# teensyMotors.net
KiCad netlist of a schematic drawn in EAGLE
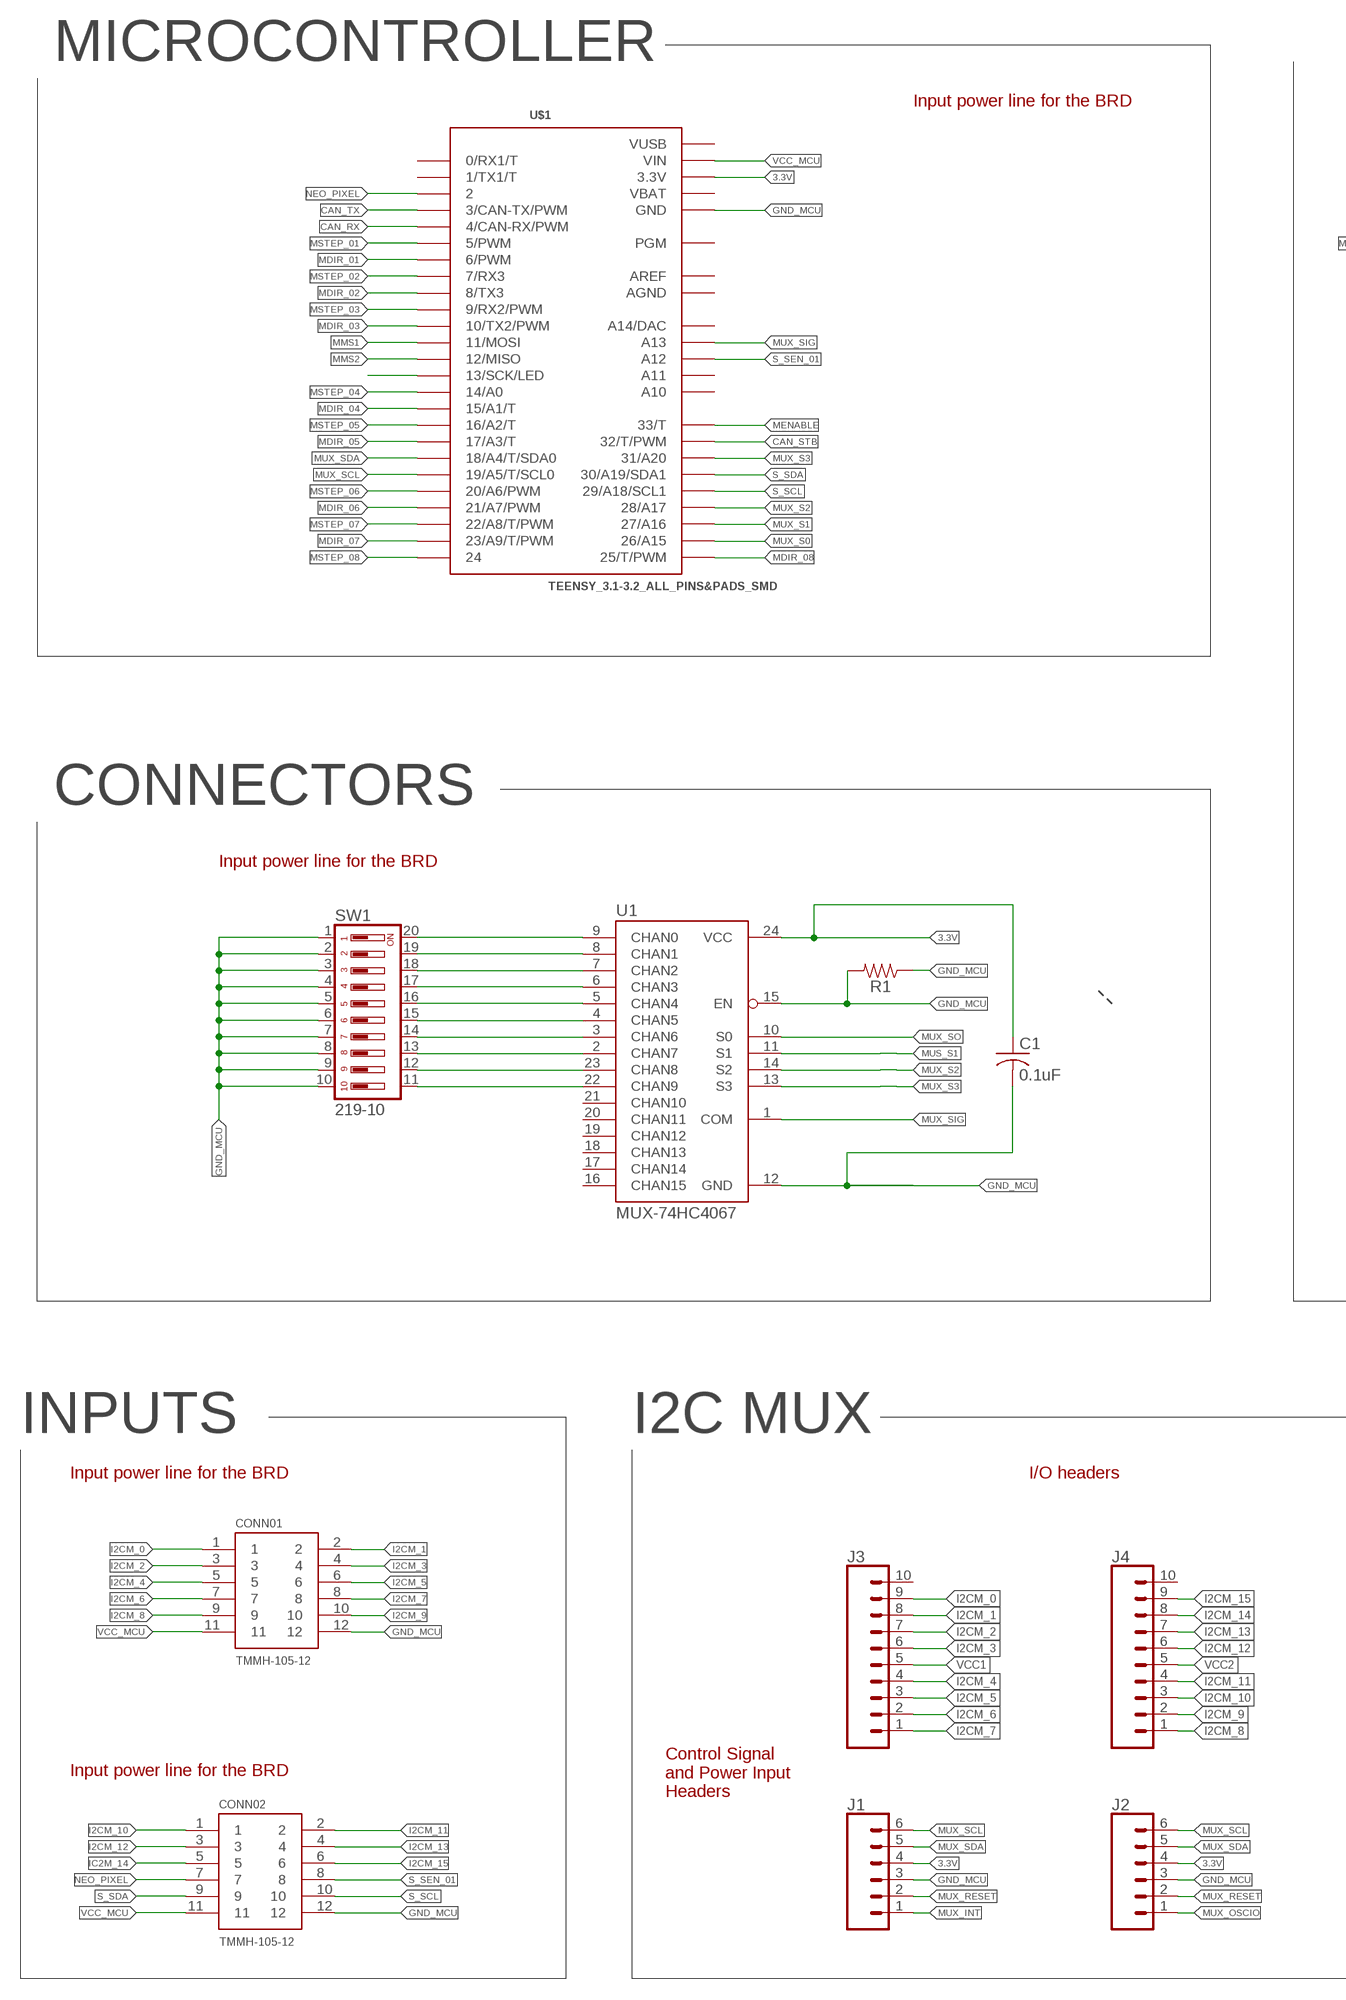
[diagram p0: schematic, sheet 1, part 1 of 2]
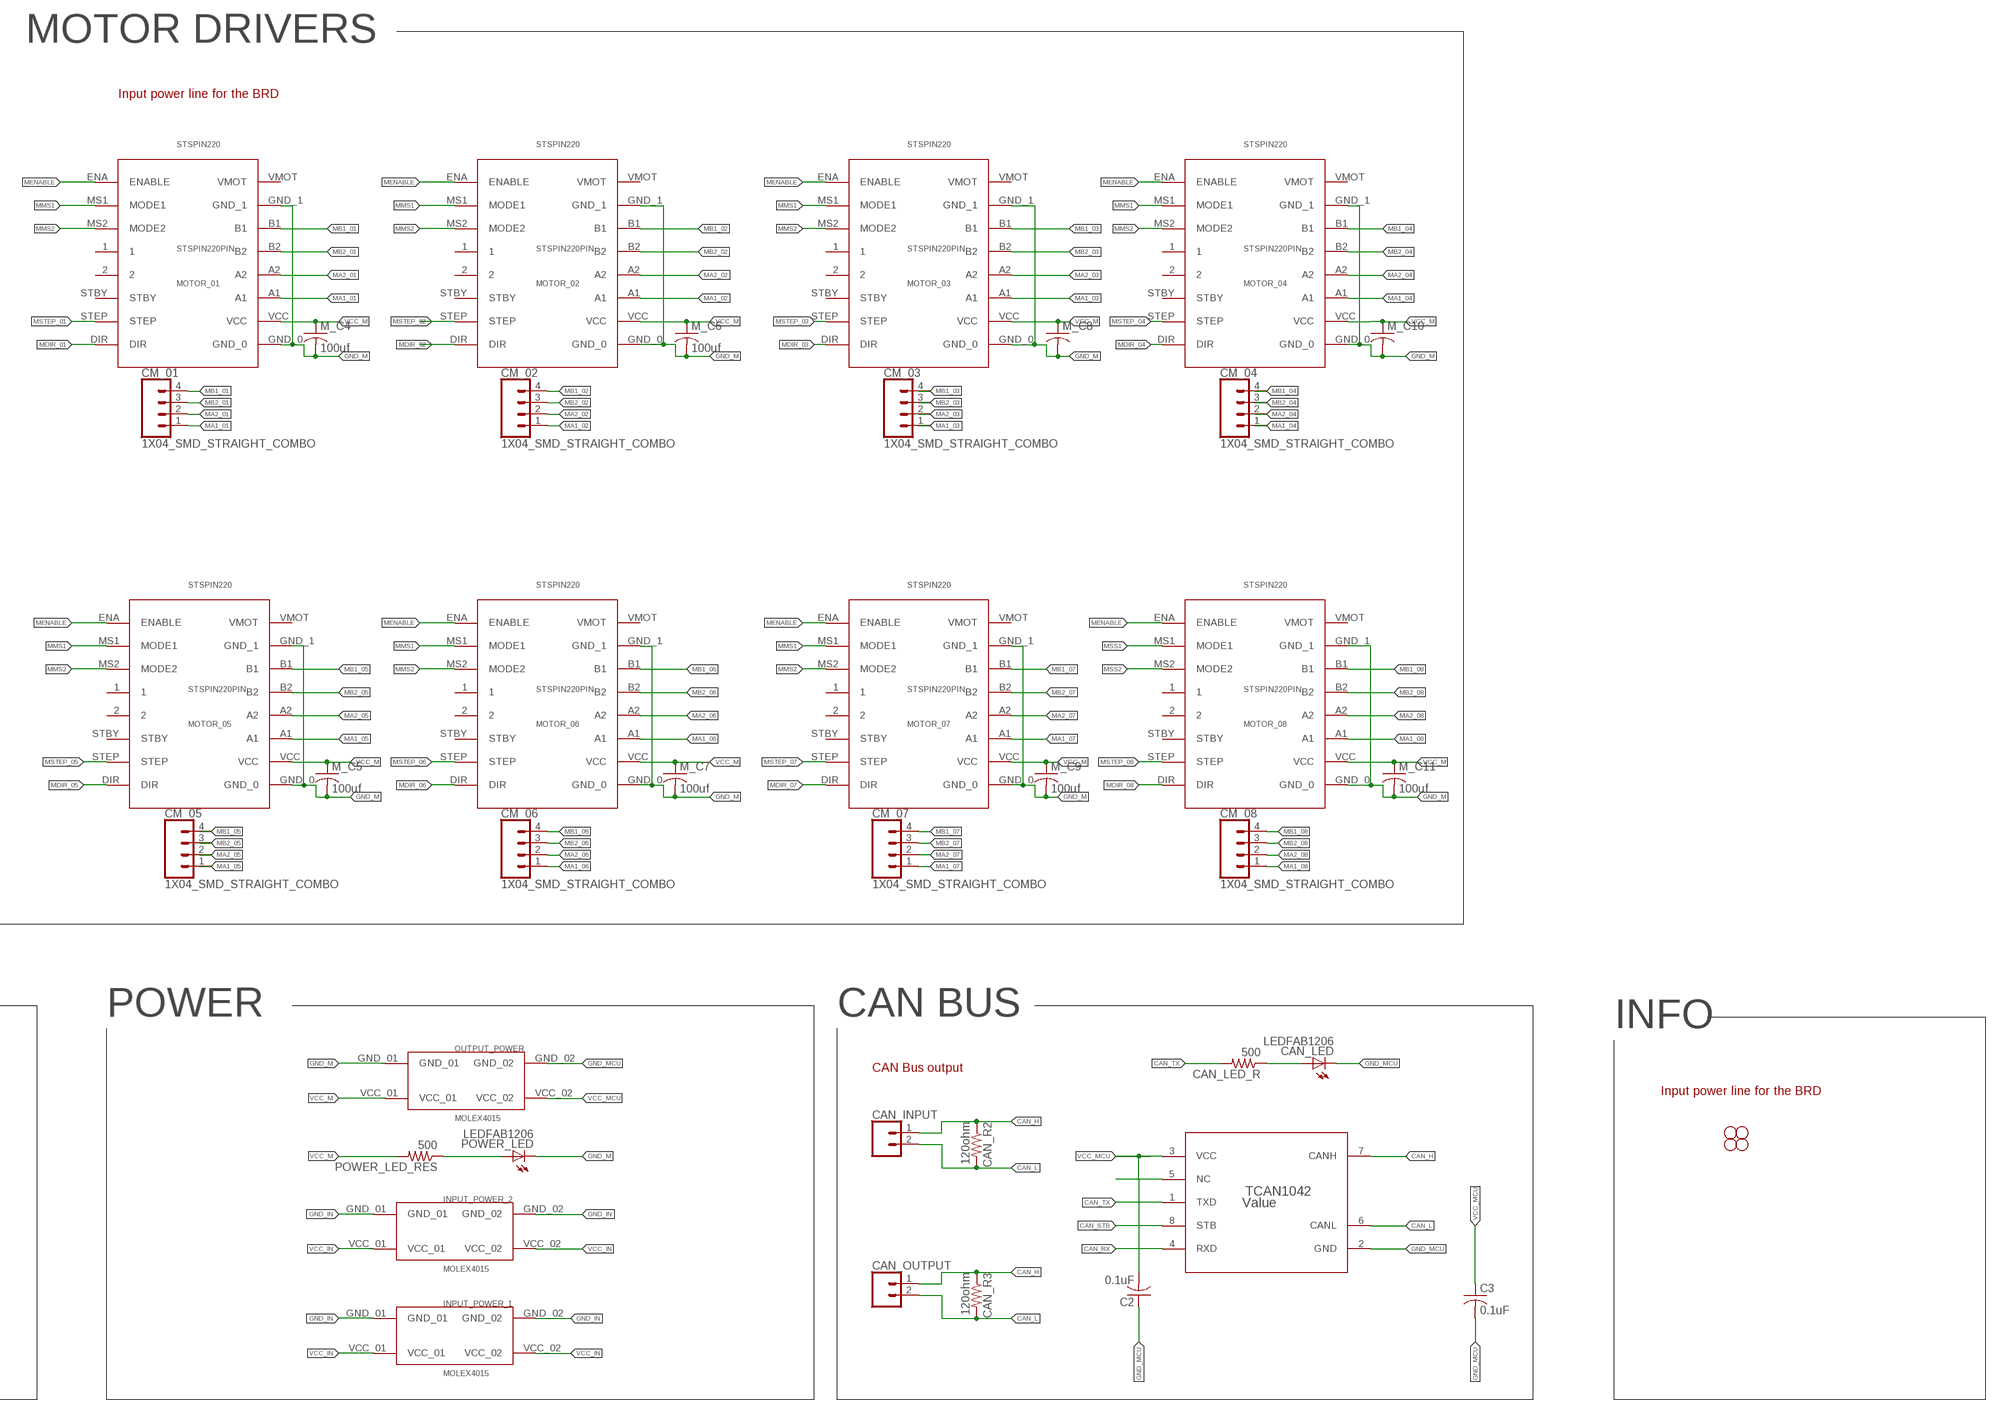
[diagram p1: schematic, sheet 1, part 2 of 2]

(export (version "E")
  (design (tool "Eeschema 10.0.6"))
  (components
    (comp (ref "C1")
      (value "0.1uF")
      (footprint "eagle-import:C1206")
      (libsource (lib "eagle-import") (part "C-USC1206"))
    )
    (comp (ref "C2")
      (value "0.1uF")
      (footprint "eagle-import:C1206")
      (libsource (lib "eagle-import") (part "C-USC1206"))
    )
    (comp (ref "C3")
      (value "0.1uF")
      (footprint "eagle-import:C1206")
      (libsource (lib "eagle-import") (part "C-USC1206"))
    )
    (comp (ref "CAN_INPUT")
      (value "CONN_02-JST-2MM-SMT")
      (footprint "eagle-import:JST-2-SMD")
      (libsource (lib "eagle-import") (part "CONN_02-JST-2MM-SMT"))
    )
    (comp (ref "CAN_LED")
      (value "LEDFAB1206")
      (footprint "eagle-import:LED1206FAB")
      (libsource (lib "eagle-import") (part "LEDFAB1206"))
    )
    (comp (ref "CAN_LED_R")
      (value "500")
      (footprint "eagle-import:R1206FAB")
      (libsource (lib "eagle-import") (part "RES-US1206FAB"))
    )
    (comp (ref "CAN_OUTPUT")
      (value "CONN_02-JST-2MM-SMT")
      (footprint "eagle-import:JST-2-SMD")
      (libsource (lib "eagle-import") (part "CONN_02-JST-2MM-SMT"))
    )
    (comp (ref "CAN_R2")
      (value "120ohm")
      (footprint "eagle-import:1206")
      (libsource (lib "eagle-import") (part "RESISTOR1206"))
    )
    (comp (ref "CAN_R3")
      (value "120ohm")
      (footprint "eagle-import:1206")
      (libsource (lib "eagle-import") (part "RESISTOR1206"))
    )
    (comp (ref "CM_01")
      (value "1X04_SMD_STRAIGHT_COMBO")
      (footprint "eagle-import:1X04_SMD_VERTICAL_COMBO")
      (libsource (lib "eagle-import") (part "CONN_04SMD_STRAIGHT_COMBO"))
    )
    (comp (ref "CM_02")
      (value "1X04_SMD_STRAIGHT_COMBO")
      (footprint "eagle-import:1X04_SMD_VERTICAL_COMBO")
      (libsource (lib "eagle-import") (part "CONN_04SMD_STRAIGHT_COMBO"))
    )
    (comp (ref "CM_03")
      (value "1X04_SMD_STRAIGHT_COMBO")
      (footprint "eagle-import:1X04_SMD_VERTICAL_COMBO")
      (libsource (lib "eagle-import") (part "CONN_04SMD_STRAIGHT_COMBO"))
    )
    (comp (ref "CM_04")
      (value "1X04_SMD_STRAIGHT_COMBO")
      (footprint "eagle-import:1X04_SMD_VERTICAL_COMBO")
      (libsource (lib "eagle-import") (part "CONN_04SMD_STRAIGHT_COMBO"))
    )
    (comp (ref "CM_05")
      (value "1X04_SMD_STRAIGHT_COMBO")
      (footprint "eagle-import:1X04_SMD_VERTICAL_COMBO")
      (libsource (lib "eagle-import") (part "CONN_04SMD_STRAIGHT_COMBO"))
    )
    (comp (ref "CM_06")
      (value "1X04_SMD_STRAIGHT_COMBO")
      (footprint "eagle-import:1X04_SMD_VERTICAL_COMBO")
      (libsource (lib "eagle-import") (part "CONN_04SMD_STRAIGHT_COMBO"))
    )
    (comp (ref "CM_07")
      (value "1X04_SMD_STRAIGHT_COMBO")
      (footprint "eagle-import:1X04_SMD_VERTICAL_COMBO")
      (libsource (lib "eagle-import") (part "CONN_04SMD_STRAIGHT_COMBO"))
    )
    (comp (ref "CM_08")
      (value "1X04_SMD_STRAIGHT_COMBO")
      (footprint "eagle-import:1X04_SMD_VERTICAL_COMBO")
      (libsource (lib "eagle-import") (part "CONN_04SMD_STRAIGHT_COMBO"))
    )
    (comp (ref "CONN01")
      (value "TMMH-105-12")
      (footprint "eagle-import:TMMH-105-12")
      (libsource (lib "eagle-import") (part "TMMH-105-12"))
    )
    (comp (ref "CONN02")
      (value "TMMH-105-12")
      (footprint "eagle-import:TMMH-105-12")
      (libsource (lib "eagle-import") (part "TMMH-105-12"))
    )
    (comp (ref "INPUT_POWER_1")
      (value "MOLEX4015")
      (footprint "eagle-import:MOLEX4015")
      (libsource (lib "eagle-import") (part "MOLEX4015"))
    )
    (comp (ref "INPUT_POWER_2")
      (value "MOLEX4015")
      (footprint "eagle-import:MOLEX4015")
      (libsource (lib "eagle-import") (part "MOLEX4015"))
    )
    (comp (ref "J1")
      (value "CONN_06SMD_MALE")
      (footprint "eagle-import:1X06_SMD_MALE")
      (libsource (lib "eagle-import") (part "CONN_06SMD_MALE"))
    )
    (comp (ref "J2")
      (value "CONN_06SMD_MALE")
      (footprint "eagle-import:1X06_SMD_MALE")
      (libsource (lib "eagle-import") (part "CONN_06SMD_MALE"))
    )
    (comp (ref "J3")
      (value "CONN_10SMD_MALE")
      (footprint "eagle-import:1X10_SMD_MALE")
      (libsource (lib "eagle-import") (part "CONN_10SMD_MALE"))
    )
    (comp (ref "J4")
      (value "CONN_10SMD_MALE")
      (footprint "eagle-import:1X10_SMD_MALE")
      (libsource (lib "eagle-import") (part "CONN_10SMD_MALE"))
    )
    (comp (ref "MOTOR_01")
      (value "STSPIN220PIN")
      (footprint "eagle-import:STSPIN220")
      (libsource (lib "eagle-import") (part "STSPIN220PIN"))
    )
    (comp (ref "MOTOR_02")
      (value "STSPIN220PIN")
      (footprint "eagle-import:STSPIN220")
      (libsource (lib "eagle-import") (part "STSPIN220PIN"))
    )
    (comp (ref "MOTOR_03")
      (value "STSPIN220PIN")
      (footprint "eagle-import:STSPIN220")
      (libsource (lib "eagle-import") (part "STSPIN220PIN"))
    )
    (comp (ref "MOTOR_04")
      (value "STSPIN220PIN")
      (footprint "eagle-import:STSPIN220")
      (libsource (lib "eagle-import") (part "STSPIN220PIN"))
    )
    (comp (ref "MOTOR_05")
      (value "STSPIN220PIN")
      (footprint "eagle-import:STSPIN220")
      (libsource (lib "eagle-import") (part "STSPIN220PIN"))
    )
    (comp (ref "MOTOR_06")
      (value "STSPIN220PIN")
      (footprint "eagle-import:STSPIN220")
      (libsource (lib "eagle-import") (part "STSPIN220PIN"))
    )
    (comp (ref "MOTOR_07")
      (value "STSPIN220PIN")
      (footprint "eagle-import:STSPIN220")
      (libsource (lib "eagle-import") (part "STSPIN220PIN"))
    )
    (comp (ref "MOTOR_08")
      (value "STSPIN220PIN")
      (footprint "eagle-import:STSPIN220")
      (libsource (lib "eagle-import") (part "STSPIN220PIN"))
    )
    (comp (ref "M_C4")
      (value "100uf")
      (footprint "eagle-import:C1206")
      (libsource (lib "eagle-import") (part "C-USC1206"))
    )
    (comp (ref "M_C5")
      (value "100uf")
      (footprint "eagle-import:C1206")
      (libsource (lib "eagle-import") (part "C-USC1206"))
    )
    (comp (ref "M_C6")
      (value "100uf")
      (footprint "eagle-import:C1206")
      (libsource (lib "eagle-import") (part "C-USC1206"))
    )
    (comp (ref "M_C7")
      (value "100uf")
      (footprint "eagle-import:C1206")
      (libsource (lib "eagle-import") (part "C-USC1206"))
    )
    (comp (ref "M_C8")
      (value "C-USC1206")
      (footprint "eagle-import:C1206")
      (libsource (lib "eagle-import") (part "C-USC1206"))
    )
    (comp (ref "M_C9")
      (value "100uf")
      (footprint "eagle-import:C1206")
      (libsource (lib "eagle-import") (part "C-USC1206"))
    )
    (comp (ref "M_C10")
      (value "C-USC1206")
      (footprint "eagle-import:C1206")
      (libsource (lib "eagle-import") (part "C-USC1206"))
    )
    (comp (ref "M_C11")
      (value "100uf")
      (footprint "eagle-import:C1206")
      (libsource (lib "eagle-import") (part "C-USC1206"))
    )
    (comp (ref "OUTPUT_POWER")
      (value "MOLEX4015")
      (footprint "eagle-import:MOLEX4015")
      (libsource (lib "eagle-import") (part "MOLEX4015"))
    )
    (comp (ref "POWER_LED")
      (value "LEDFAB1206")
      (footprint "eagle-import:LED1206FAB")
      (libsource (lib "eagle-import") (part "LEDFAB1206"))
    )
    (comp (ref "POWER_LED_RES")
      (value "500")
      (footprint "eagle-import:R1206FAB")
      (libsource (lib "eagle-import") (part "RES-US1206FAB"))
    )
    (comp (ref "R1")
      (value "RESISTOR1206")
      (footprint "eagle-import:1206")
      (libsource (lib "eagle-import") (part "RESISTOR1206"))
    )
    (comp (ref "STANDOFF5")
      (value "STAND-OFF")
      (footprint "eagle-import:STAND-OFF")
      (libsource (lib "eagle-import") (part "STAND-OFF"))
    )
    (comp (ref "STANDOFF6")
      (value "STAND-OFF")
      (footprint "eagle-import:STAND-OFF")
      (libsource (lib "eagle-import") (part "STAND-OFF"))
    )
    (comp (ref "STANDOFF7")
      (value "STAND-OFF")
      (footprint "eagle-import:STAND-OFF")
      (libsource (lib "eagle-import") (part "STAND-OFF"))
    )
    (comp (ref "STANDOFF8")
      (value "STAND-OFF")
      (footprint "eagle-import:STAND-OFF")
      (libsource (lib "eagle-import") (part "STAND-OFF"))
    )
    (comp (ref "SW1")
      (value "219-10")
      (footprint "eagle-import:CTS-219-10")
      (fields (field (name "MF") "SLI (CML/IDI)") (field (name "MPN") "219-10PK"))
      (libsource (lib "eagle-import") (part "219-10"))
    )
    (comp (ref "TCAN1042")
      (value "Value")
      (footprint "eagle-import:D0008A_N")
      (fields (field (name "MANUFACTURER") "Texas Instruments") (field (name "PARTNUMBER") "TCAN1042DRQ1"))
      (libsource (lib "eagle-import") (part "TCAN1042DRQ1"))
    )
    (comp (ref "U$1")
      (value "TEENSY_3.1-3.2_ALL_PINS&PADS_SMD")
      (footprint "eagle-import:TEENSY_3.0-3.2_ALL_PINS_&_PADS_SMD")
      (libsource (lib "eagle-import") (part "TEENSY_3.1-3.2_ALL_PINS&PADS_SMD"))
    )
    (comp (ref "U1")
      (value "MUX-74HC4067")
      (footprint "eagle-import:SSOP24")
      (libsource (lib "eagle-import") (part "MUX-74HC4067SMD"))
    )
  )
  (nets
    (net (code "1") (name "/AGND") (class "Default")
      (node (ref "U$1") (pin "AGND") (pinfunction "AGND_AGND") (pintype "power_in"))
    )
    (net (code "2") (name "/AREF") (class "Default")
      (node (ref "U$1") (pin "AREF") (pinfunction "AREF_AREF") (pintype "power_in"))
    )
    (net (code "3") (name "/VBAT") (class "Default")
      (node (ref "U$1") (pin "VBAT") (pinfunction "VBAT_VBAT") (pintype "power_in"))
    )
    (net (code "4") (name "/VUSB") (class "Default")
      (node (ref "U$1") (pin "VUSB") (pinfunction "VUSB_VUSB") (pintype "power_in"))
    )
    (net (code "5") (name "3.3V") (class "Default")
      (node (ref "C1") (pin "1") (pinfunction "1_1") (pintype "passive"))
      (node (ref "J1") (pin "4") (pinfunction "4_4") (pintype "passive"))
      (node (ref "J2") (pin "4") (pinfunction "4_4") (pintype "passive"))
      (node (ref "U$1") (pin "3.3V") (pinfunction "3.3V_3.3V") (pintype "power_in"))
      (node (ref "U$1") (pin "3.3V1") (pinfunction "3.3V_3.3V1") (pintype "power_in"))
      (node (ref "U$1") (pin "3.3V2") (pinfunction "3.3V_3.3V2") (pintype "power_in"))
      (node (ref "U1") (pin "24") (pinfunction "VCC_24") (pintype "bidirectional"))
    )
    (net (code "6") (name "CAN_H") (class "Default")
      (node (ref "CAN_INPUT") (pin "1") (pinfunction "2_1") (pintype "passive"))
      (node (ref "CAN_OUTPUT") (pin "1") (pinfunction "2_1") (pintype "passive"))
      (node (ref "CAN_R2") (pin "1") (pinfunction "1_1") (pintype "passive"))
      (node (ref "CAN_R3") (pin "1") (pinfunction "1_1") (pintype "passive"))
      (node (ref "TCAN1042") (pin "7") (pinfunction "CANH_7") (pintype "bidirectional"))
    )
    (net (code "7") (name "CAN_L") (class "Default")
      (node (ref "CAN_INPUT") (pin "2") (pinfunction "1_2") (pintype "passive"))
      (node (ref "CAN_OUTPUT") (pin "2") (pinfunction "1_2") (pintype "passive"))
      (node (ref "CAN_R2") (pin "2") (pinfunction "2_2") (pintype "passive"))
      (node (ref "CAN_R3") (pin "2") (pinfunction "2_2") (pintype "passive"))
      (node (ref "TCAN1042") (pin "6") (pinfunction "CANL_6") (pintype "bidirectional"))
    )
    (net (code "8") (name "CAN_RX") (class "Default")
      (node (ref "TCAN1042") (pin "4") (pinfunction "RXD_4") (pintype "output"))
      (node (ref "U$1") (pin "4") (pinfunction "4/CAN-RX/PWM_4") (pintype "bidirectional"))
    )
    (net (code "9") (name "CAN_STB") (class "Default")
      (node (ref "TCAN1042") (pin "8") (pinfunction "STB_8") (pintype "input"))
      (node (ref "U$1") (pin "32") (pinfunction "32/T/PWM_32") (pintype "bidirectional"))
    )
    (net (code "10") (name "CAN_TX") (class "Default")
      (node (ref "CAN_LED_R") (pin "2") (pinfunction "2_2") (pintype "passive"))
      (node (ref "TCAN1042") (pin "1") (pinfunction "TXD_1") (pintype "input"))
      (node (ref "U$1") (pin "3") (pinfunction "3/CAN-TX/PWM_3") (pintype "bidirectional"))
    )
    (net (code "11") (name "GND_IN") (class "Default")
      (node (ref "INPUT_POWER_1") (pin "GND_01") (pinfunction "GND_01_GND_01") (pintype "bidirectional"))
      (node (ref "INPUT_POWER_1") (pin "GND_02") (pinfunction "GND_02_GND_02") (pintype "bidirectional"))
      (node (ref "INPUT_POWER_2") (pin "GND_01") (pinfunction "GND_01_GND_01") (pintype "bidirectional"))
      (node (ref "INPUT_POWER_2") (pin "GND_02") (pinfunction "GND_02_GND_02") (pintype "bidirectional"))
    )
    (net (code "12") (name "GND_M") (class "Default")
      (node (ref "MOTOR_01") (pin "GND_0") (pinfunction "GND_0_GND_0") (pintype "bidirectional"))
      (node (ref "MOTOR_01") (pin "GND_1") (pinfunction "GND_1_GND_1") (pintype "bidirectional"))
      (node (ref "MOTOR_02") (pin "GND_0") (pinfunction "GND_0_GND_0") (pintype "bidirectional"))
      (node (ref "MOTOR_02") (pin "GND_1") (pinfunction "GND_1_GND_1") (pintype "bidirectional"))
      (node (ref "MOTOR_03") (pin "GND_0") (pinfunction "GND_0_GND_0") (pintype "bidirectional"))
      (node (ref "MOTOR_03") (pin "GND_1") (pinfunction "GND_1_GND_1") (pintype "bidirectional"))
      (node (ref "MOTOR_04") (pin "GND_0") (pinfunction "GND_0_GND_0") (pintype "bidirectional"))
      (node (ref "MOTOR_04") (pin "GND_1") (pinfunction "GND_1_GND_1") (pintype "bidirectional"))
      (node (ref "MOTOR_05") (pin "GND_0") (pinfunction "GND_0_GND_0") (pintype "bidirectional"))
      (node (ref "MOTOR_05") (pin "GND_1") (pinfunction "GND_1_GND_1") (pintype "bidirectional"))
      (node (ref "MOTOR_06") (pin "GND_0") (pinfunction "GND_0_GND_0") (pintype "bidirectional"))
      (node (ref "MOTOR_06") (pin "GND_1") (pinfunction "GND_1_GND_1") (pintype "bidirectional"))
      (node (ref "MOTOR_07") (pin "GND_0") (pinfunction "GND_0_GND_0") (pintype "bidirectional"))
      (node (ref "MOTOR_07") (pin "GND_1") (pinfunction "GND_1_GND_1") (pintype "bidirectional"))
      (node (ref "MOTOR_08") (pin "GND_0") (pinfunction "GND_0_GND_0") (pintype "bidirectional"))
      (node (ref "MOTOR_08") (pin "GND_1") (pinfunction "GND_1_GND_1") (pintype "bidirectional"))
      (node (ref "M_C10") (pin "2") (pinfunction "2_2") (pintype "passive"))
      (node (ref "M_C11") (pin "2") (pinfunction "2_2") (pintype "passive"))
      (node (ref "M_C4") (pin "2") (pinfunction "2_2") (pintype "passive"))
      (node (ref "M_C5") (pin "2") (pinfunction "2_2") (pintype "passive"))
      (node (ref "M_C6") (pin "2") (pinfunction "2_2") (pintype "passive"))
      (node (ref "M_C7") (pin "2") (pinfunction "2_2") (pintype "passive"))
      (node (ref "M_C8") (pin "2") (pinfunction "2_2") (pintype "passive"))
      (node (ref "M_C9") (pin "2") (pinfunction "2_2") (pintype "passive"))
      (node (ref "OUTPUT_POWER") (pin "GND_01") (pinfunction "GND_01_GND_01") (pintype "bidirectional"))
      (node (ref "POWER_LED") (pin "2") (pinfunction "C_2") (pintype "passive"))
    )
    (net (code "13") (name "GND_MCU") (class "Default")
      (node (ref "C1") (pin "2") (pinfunction "2_2") (pintype "passive"))
      (node (ref "C2") (pin "1") (pinfunction "1_1") (pintype "passive"))
      (node (ref "C3") (pin "2") (pinfunction "2_2") (pintype "passive"))
      (node (ref "CAN_LED") (pin "2") (pinfunction "C_2") (pintype "passive"))
      (node (ref "CONN01") (pin "12") (pinfunction "12_12") (pintype "bidirectional"))
      (node (ref "CONN02") (pin "12") (pinfunction "12_12") (pintype "bidirectional"))
      (node (ref "J1") (pin "3") (pinfunction "3_3") (pintype "passive"))
      (node (ref "J2") (pin "3") (pinfunction "3_3") (pintype "passive"))
      (node (ref "OUTPUT_POWER") (pin "GND_02") (pinfunction "GND_02_GND_02") (pintype "bidirectional"))
      (node (ref "R1") (pin "1") (pinfunction "1_1") (pintype "passive"))
      (node (ref "R1") (pin "2") (pinfunction "2_2") (pintype "passive"))
      (node (ref "SW1") (pin "1") (pinfunction "1_1") (pintype "passive"))
      (node (ref "SW1") (pin "10") (pinfunction "10_10") (pintype "passive"))
      (node (ref "SW1") (pin "2") (pinfunction "2_2") (pintype "passive"))
      (node (ref "SW1") (pin "3") (pinfunction "3_3") (pintype "passive"))
      (node (ref "SW1") (pin "4") (pinfunction "4_4") (pintype "passive"))
      (node (ref "SW1") (pin "5") (pinfunction "5_5") (pintype "passive"))
      (node (ref "SW1") (pin "6") (pinfunction "6_6") (pintype "passive"))
      (node (ref "SW1") (pin "7") (pinfunction "7_7") (pintype "passive"))
      (node (ref "SW1") (pin "8") (pinfunction "8_8") (pintype "passive"))
      (node (ref "SW1") (pin "9") (pinfunction "9_9") (pintype "passive"))
      (node (ref "TCAN1042") (pin "2") (pinfunction "GND_2") (pintype "power_in"))
      (node (ref "U$1") (pin "GND") (pinfunction "GND_GND") (pintype "power_in"))
      (node (ref "U$1") (pin "GND1") (pinfunction "GND_GND1") (pintype "power_in"))
      (node (ref "U$1") (pin "GND2") (pinfunction "GND_GND2") (pintype "power_in"))
      (node (ref "U1") (pin "12") (pinfunction "GND_12") (pintype "bidirectional"))
      (node (ref "U1") (pin "15") (pinfunction "EN_15") (pintype "input"))
    )
    (net (code "14") (name "I2CM_0") (class "Default")
      (node (ref "CONN01") (pin "1") (pinfunction "1_1") (pintype "bidirectional"))
      (node (ref "J3") (pin "9") (pinfunction "9_9") (pintype "passive"))
    )
    (net (code "15") (name "I2CM_1") (class "Default")
      (node (ref "CONN01") (pin "2") (pinfunction "2_2") (pintype "bidirectional"))
      (node (ref "J3") (pin "8") (pinfunction "8_8") (pintype "passive"))
    )
    (net (code "16") (name "I2CM_2") (class "Default")
      (node (ref "CONN01") (pin "3") (pinfunction "3_3") (pintype "bidirectional"))
      (node (ref "J3") (pin "7") (pinfunction "7_7") (pintype "passive"))
    )
    (net (code "17") (name "I2CM_3") (class "Default")
      (node (ref "CONN01") (pin "4") (pinfunction "4_4") (pintype "bidirectional"))
      (node (ref "J3") (pin "6") (pinfunction "6_6") (pintype "passive"))
    )
    (net (code "18") (name "I2CM_4") (class "Default")
      (node (ref "CONN01") (pin "5") (pinfunction "5_5") (pintype "bidirectional"))
      (node (ref "J3") (pin "4") (pinfunction "4_4") (pintype "passive"))
    )
    (net (code "19") (name "I2CM_5") (class "Default")
      (node (ref "CONN01") (pin "6") (pinfunction "6_6") (pintype "bidirectional"))
      (node (ref "J3") (pin "3") (pinfunction "3_3") (pintype "passive"))
    )
    (net (code "20") (name "I2CM_6") (class "Default")
      (node (ref "CONN01") (pin "7") (pinfunction "7_7") (pintype "bidirectional"))
      (node (ref "J3") (pin "2") (pinfunction "2_2") (pintype "passive"))
    )
    (net (code "21") (name "I2CM_7") (class "Default")
      (node (ref "CONN01") (pin "8") (pinfunction "8_8") (pintype "bidirectional"))
      (node (ref "J3") (pin "1") (pinfunction "1_1") (pintype "passive"))
    )
    (net (code "22") (name "I2CM_8") (class "Default")
      (node (ref "CONN01") (pin "9") (pinfunction "9_9") (pintype "bidirectional"))
      (node (ref "J4") (pin "1") (pinfunction "1_1") (pintype "passive"))
    )
    (net (code "23") (name "I2CM_9") (class "Default")
      (node (ref "CONN01") (pin "10") (pinfunction "10_10") (pintype "bidirectional"))
      (node (ref "J4") (pin "2") (pinfunction "2_2") (pintype "passive"))
    )
    (net (code "24") (name "I2CM_10") (class "Default")
      (node (ref "CONN02") (pin "1") (pinfunction "1_1") (pintype "bidirectional"))
      (node (ref "J4") (pin "3") (pinfunction "3_3") (pintype "passive"))
    )
    (net (code "25") (name "I2CM_11") (class "Default")
      (node (ref "CONN02") (pin "2") (pinfunction "2_2") (pintype "bidirectional"))
      (node (ref "J4") (pin "4") (pinfunction "4_4") (pintype "passive"))
    )
    (net (code "26") (name "I2CM_12") (class "Default")
      (node (ref "CONN02") (pin "3") (pinfunction "3_3") (pintype "bidirectional"))
      (node (ref "J4") (pin "6") (pinfunction "6_6") (pintype "passive"))
    )
    (net (code "27") (name "I2CM_13") (class "Default")
      (node (ref "CONN02") (pin "4") (pinfunction "4_4") (pintype "bidirectional"))
      (node (ref "J4") (pin "7") (pinfunction "7_7") (pintype "passive"))
    )
    (net (code "28") (name "I2CM_14") (class "Default")
      (node (ref "J4") (pin "8") (pinfunction "8_8") (pintype "passive"))
    )
    (net (code "29") (name "I2CM_15") (class "Default")
      (node (ref "CONN02") (pin "6") (pinfunction "6_6") (pintype "bidirectional"))
      (node (ref "J4") (pin "9") (pinfunction "9_9") (pintype "passive"))
    )
    (net (code "30") (name "IC2M_14") (class "Default")
      (node (ref "CONN02") (pin "5") (pinfunction "5_5") (pintype "bidirectional"))
    )
    (net (code "31") (name "MA1_01") (class "Default")
      (node (ref "CM_01") (pin "1") (pinfunction "1_1") (pintype "passive"))
      (node (ref "MOTOR_01") (pin "A1") (pinfunction "A1_A1") (pintype "bidirectional"))
    )
    (net (code "32") (name "MA1_02") (class "Default")
      (node (ref "CM_02") (pin "1") (pinfunction "1_1") (pintype "passive"))
      (node (ref "MOTOR_02") (pin "A1") (pinfunction "A1_A1") (pintype "bidirectional"))
    )
    (net (code "33") (name "MA1_03") (class "Default")
      (node (ref "CM_03") (pin "1") (pinfunction "1_1") (pintype "passive"))
      (node (ref "MOTOR_03") (pin "A1") (pinfunction "A1_A1") (pintype "bidirectional"))
    )
    (net (code "34") (name "MA1_04") (class "Default")
      (node (ref "CM_04") (pin "1") (pinfunction "1_1") (pintype "passive"))
      (node (ref "MOTOR_04") (pin "A1") (pinfunction "A1_A1") (pintype "bidirectional"))
    )
    (net (code "35") (name "MA1_05") (class "Default")
      (node (ref "CM_05") (pin "1") (pinfunction "1_1") (pintype "passive"))
      (node (ref "MOTOR_05") (pin "A1") (pinfunction "A1_A1") (pintype "bidirectional"))
    )
    (net (code "36") (name "MA1_06") (class "Default")
      (node (ref "CM_06") (pin "1") (pinfunction "1_1") (pintype "passive"))
      (node (ref "MOTOR_06") (pin "A1") (pinfunction "A1_A1") (pintype "bidirectional"))
    )
    (net (code "37") (name "MA1_07") (class "Default")
      (node (ref "CM_07") (pin "1") (pinfunction "1_1") (pintype "passive"))
      (node (ref "MOTOR_07") (pin "A1") (pinfunction "A1_A1") (pintype "bidirectional"))
    )
    (net (code "38") (name "MA1_08") (class "Default")
      (node (ref "CM_08") (pin "1") (pinfunction "1_1") (pintype "passive"))
      (node (ref "MOTOR_08") (pin "A1") (pinfunction "A1_A1") (pintype "bidirectional"))
    )
    (net (code "39") (name "MA2_01") (class "Default")
      (node (ref "CM_01") (pin "2") (pinfunction "2_2") (pintype "passive"))
      (node (ref "MOTOR_01") (pin "A2") (pinfunction "A2_A2") (pintype "bidirectional"))
    )
    (net (code "40") (name "MA2_02") (class "Default")
      (node (ref "CM_02") (pin "2") (pinfunction "2_2") (pintype "passive"))
      (node (ref "MOTOR_02") (pin "A2") (pinfunction "A2_A2") (pintype "bidirectional"))
    )
    (net (code "41") (name "MA2_03") (class "Default")
      (node (ref "CM_03") (pin "2") (pinfunction "2_2") (pintype "passive"))
      (node (ref "MOTOR_03") (pin "A2") (pinfunction "A2_A2") (pintype "bidirectional"))
    )
    (net (code "42") (name "MA2_04") (class "Default")
      (node (ref "CM_04") (pin "2") (pinfunction "2_2") (pintype "passive"))
      (node (ref "MOTOR_04") (pin "A2") (pinfunction "A2_A2") (pintype "bidirectional"))
    )
    (net (code "43") (name "MA2_05") (class "Default")
      (node (ref "CM_05") (pin "2") (pinfunction "2_2") (pintype "passive"))
      (node (ref "MOTOR_05") (pin "A2") (pinfunction "A2_A2") (pintype "bidirectional"))
    )
    (net (code "44") (name "MA2_06") (class "Default")
      (node (ref "CM_06") (pin "2") (pinfunction "2_2") (pintype "passive"))
      (node (ref "MOTOR_06") (pin "A2") (pinfunction "A2_A2") (pintype "bidirectional"))
    )
    (net (code "45") (name "MA2_07") (class "Default")
      (node (ref "CM_07") (pin "2") (pinfunction "2_2") (pintype "passive"))
      (node (ref "MOTOR_07") (pin "A2") (pinfunction "A2_A2") (pintype "bidirectional"))
    )
    (net (code "46") (name "MA2_08") (class "Default")
      (node (ref "CM_08") (pin "2") (pinfunction "2_2") (pintype "passive"))
      (node (ref "MOTOR_08") (pin "A2") (pinfunction "A2_A2") (pintype "bidirectional"))
    )
    (net (code "47") (name "MB1_01") (class "Default")
      (node (ref "CM_01") (pin "4") (pinfunction "4_4") (pintype "passive"))
      (node (ref "MOTOR_01") (pin "B1") (pinfunction "B1_B1") (pintype "bidirectional"))
    )
    (net (code "48") (name "MB1_02") (class "Default")
      (node (ref "CM_02") (pin "4") (pinfunction "4_4") (pintype "passive"))
      (node (ref "MOTOR_02") (pin "B1") (pinfunction "B1_B1") (pintype "bidirectional"))
    )
    (net (code "49") (name "MB1_03") (class "Default")
      (node (ref "CM_03") (pin "4") (pinfunction "4_4") (pintype "passive"))
      (node (ref "MOTOR_03") (pin "B1") (pinfunction "B1_B1") (pintype "bidirectional"))
    )
    (net (code "50") (name "MB1_04") (class "Default")
      (node (ref "CM_04") (pin "4") (pinfunction "4_4") (pintype "passive"))
      (node (ref "MOTOR_04") (pin "B1") (pinfunction "B1_B1") (pintype "bidirectional"))
    )
    (net (code "51") (name "MB1_05") (class "Default")
      (node (ref "CM_05") (pin "4") (pinfunction "4_4") (pintype "passive"))
      (node (ref "MOTOR_05") (pin "B1") (pinfunction "B1_B1") (pintype "bidirectional"))
    )
    (net (code "52") (name "MB1_06") (class "Default")
      (node (ref "CM_06") (pin "4") (pinfunction "4_4") (pintype "passive"))
      (node (ref "MOTOR_06") (pin "B1") (pinfunction "B1_B1") (pintype "bidirectional"))
    )
    (net (code "53") (name "MB1_07") (class "Default")
      (node (ref "CM_07") (pin "4") (pinfunction "4_4") (pintype "passive"))
      (node (ref "MOTOR_07") (pin "B1") (pinfunction "B1_B1") (pintype "bidirectional"))
    )
    (net (code "54") (name "MB1_08") (class "Default")
      (node (ref "CM_08") (pin "4") (pinfunction "4_4") (pintype "passive"))
      (node (ref "MOTOR_08") (pin "B1") (pinfunction "B1_B1") (pintype "bidirectional"))
    )
    (net (code "55") (name "MB2_01") (class "Default")
      (node (ref "CM_01") (pin "3") (pinfunction "3_3") (pintype "passive"))
      (node (ref "MOTOR_01") (pin "B2") (pinfunction "B2_B2") (pintype "bidirectional"))
    )
    (net (code "56") (name "MB2_02") (class "Default")
      (node (ref "CM_02") (pin "3") (pinfunction "3_3") (pintype "passive"))
      (node (ref "MOTOR_02") (pin "B2") (pinfunction "B2_B2") (pintype "bidirectional"))
    )
    (net (code "57") (name "MB2_03") (class "Default")
      (node (ref "CM_03") (pin "3") (pinfunction "3_3") (pintype "passive"))
      (node (ref "MOTOR_03") (pin "B2") (pinfunction "B2_B2") (pintype "bidirectional"))
    )
    (net (code "58") (name "MB2_04") (class "Default")
      (node (ref "CM_04") (pin "3") (pinfunction "3_3") (pintype "passive"))
      (node (ref "MOTOR_04") (pin "B2") (pinfunction "B2_B2") (pintype "bidirectional"))
    )
    (net (code "59") (name "MB2_05") (class "Default")
      (node (ref "CM_05") (pin "3") (pinfunction "3_3") (pintype "passive"))
      (node (ref "MOTOR_05") (pin "B2") (pinfunction "B2_B2") (pintype "bidirectional"))
    )
    (net (code "60") (name "MB2_06") (class "Default")
      (node (ref "CM_06") (pin "3") (pinfunction "3_3") (pintype "passive"))
      (node (ref "MOTOR_06") (pin "B2") (pinfunction "B2_B2") (pintype "bidirectional"))
    )
    (net (code "61") (name "MB2_07") (class "Default")
      (node (ref "CM_07") (pin "3") (pinfunction "3_3") (pintype "passive"))
      (node (ref "MOTOR_07") (pin "B2") (pinfunction "B2_B2") (pintype "bidirectional"))
    )
    (net (code "62") (name "MB2_08") (class "Default")
      (node (ref "CM_08") (pin "3") (pinfunction "3_3") (pintype "passive"))
      (node (ref "MOTOR_08") (pin "B2") (pinfunction "B2_B2") (pintype "bidirectional"))
    )
    (net (code "63") (name "MDIR_01") (class "Default")
      (node (ref "MOTOR_01") (pin "DIR") (pinfunction "DIR_DIR") (pintype "bidirectional"))
      (node (ref "U$1") (pin "6") (pinfunction "6/PWM_6") (pintype "bidirectional"))
    )
    (net (code "64") (name "MDIR_02") (class "Default")
      (node (ref "MOTOR_02") (pin "DIR") (pinfunction "DIR_DIR") (pintype "bidirectional"))
      (node (ref "U$1") (pin "8") (pinfunction "8/TX3_8") (pintype "bidirectional"))
    )
    (net (code "65") (name "MDIR_03") (class "Default")
      (node (ref "MOTOR_03") (pin "DIR") (pinfunction "DIR_DIR") (pintype "bidirectional"))
      (node (ref "U$1") (pin "10") (pinfunction "10/TX2/PWM_10") (pintype "bidirectional"))
    )
    (net (code "66") (name "MDIR_04") (class "Default")
      (node (ref "MOTOR_04") (pin "DIR") (pinfunction "DIR_DIR") (pintype "bidirectional"))
      (node (ref "U$1") (pin "15/A1") (pinfunction "15/A1/T_15/A1") (pintype "bidirectional"))
    )
    (net (code "67") (name "MDIR_05") (class "Default")
      (node (ref "MOTOR_05") (pin "DIR") (pinfunction "DIR_DIR") (pintype "bidirectional"))
      (node (ref "U$1") (pin "17/A3") (pinfunction "17/A3/T_17/A3") (pintype "bidirectional"))
    )
    (net (code "68") (name "MDIR_06") (class "Default")
      (node (ref "MOTOR_06") (pin "DIR") (pinfunction "DIR_DIR") (pintype "bidirectional"))
      (node (ref "U$1") (pin "21/A7") (pinfunction "21/A7/PWM_21/A7") (pintype "bidirectional"))
    )
    (net (code "69") (name "MDIR_07") (class "Default")
      (node (ref "MOTOR_07") (pin "DIR") (pinfunction "DIR_DIR") (pintype "bidirectional"))
      (node (ref "U$1") (pin "23/A9") (pinfunction "23/A9/T/PWM_23/A9") (pintype "bidirectional"))
    )
    (net (code "70") (name "MDIR_08") (class "Default")
      (node (ref "MOTOR_08") (pin "DIR") (pinfunction "DIR_DIR") (pintype "bidirectional"))
      (node (ref "U$1") (pin "25") (pinfunction "25/T/PWM_25") (pintype "bidirectional"))
    )
    (net (code "71") (name "MENABLE") (class "Default")
      (node (ref "MOTOR_01") (pin "ENA") (pinfunction "ENABLE_ENA") (pintype "bidirectional"))
      (node (ref "MOTOR_02") (pin "ENA") (pinfunction "ENABLE_ENA") (pintype "bidirectional"))
      (node (ref "MOTOR_03") (pin "ENA") (pinfunction "ENABLE_ENA") (pintype "bidirectional"))
      (node (ref "MOTOR_04") (pin "ENA") (pinfunction "ENABLE_ENA") (pintype "bidirectional"))
      (node (ref "MOTOR_05") (pin "ENA") (pinfunction "ENABLE_ENA") (pintype "bidirectional"))
      (node (ref "MOTOR_06") (pin "ENA") (pinfunction "ENABLE_ENA") (pintype "bidirectional"))
      (node (ref "MOTOR_07") (pin "ENA") (pinfunction "ENABLE_ENA") (pintype "bidirectional"))
      (node (ref "MOTOR_08") (pin "ENA") (pinfunction "ENABLE_ENA") (pintype "bidirectional"))
      (node (ref "U$1") (pin "33") (pinfunction "33/T_33") (pintype "bidirectional"))
    )
    (net (code "72") (name "MMS1") (class "Default")
      (node (ref "MOTOR_01") (pin "MS1") (pinfunction "MODE1_MS1") (pintype "bidirectional"))
      (node (ref "MOTOR_02") (pin "MS1") (pinfunction "MODE1_MS1") (pintype "bidirectional"))
      (node (ref "MOTOR_03") (pin "MS1") (pinfunction "MODE1_MS1") (pintype "bidirectional"))
      (node (ref "MOTOR_04") (pin "MS1") (pinfunction "MODE1_MS1") (pintype "bidirectional"))
      (node (ref "MOTOR_05") (pin "MS1") (pinfunction "MODE1_MS1") (pintype "bidirectional"))
      (node (ref "MOTOR_06") (pin "MS1") (pinfunction "MODE1_MS1") (pintype "bidirectional"))
      (node (ref "MOTOR_07") (pin "MS1") (pinfunction "MODE1_MS1") (pintype "bidirectional"))
      (node (ref "U$1") (pin "11") (pinfunction "11/MOSI_11") (pintype "bidirectional"))
    )
    (net (code "73") (name "MMS2") (class "Default")
      (node (ref "MOTOR_01") (pin "MS2") (pinfunction "MODE2_MS2") (pintype "bidirectional"))
      (node (ref "MOTOR_02") (pin "MS2") (pinfunction "MODE2_MS2") (pintype "bidirectional"))
      (node (ref "MOTOR_03") (pin "MS2") (pinfunction "MODE2_MS2") (pintype "bidirectional"))
      (node (ref "MOTOR_04") (pin "MS2") (pinfunction "MODE2_MS2") (pintype "bidirectional"))
      (node (ref "MOTOR_05") (pin "MS2") (pinfunction "MODE2_MS2") (pintype "bidirectional"))
      (node (ref "MOTOR_06") (pin "MS2") (pinfunction "MODE2_MS2") (pintype "bidirectional"))
      (node (ref "MOTOR_07") (pin "MS2") (pinfunction "MODE2_MS2") (pintype "bidirectional"))
      (node (ref "U$1") (pin "12") (pinfunction "12/MISO_12") (pintype "bidirectional"))
    )
    (net (code "74") (name "MSS1") (class "Default")
      (node (ref "MOTOR_08") (pin "MS1") (pinfunction "MODE1_MS1") (pintype "bidirectional"))
    )
    (net (code "75") (name "MSS2") (class "Default")
      (node (ref "MOTOR_08") (pin "MS2") (pinfunction "MODE2_MS2") (pintype "bidirectional"))
    )
    (net (code "76") (name "MSTEP_01") (class "Default")
      (node (ref "MOTOR_01") (pin "STEP") (pinfunction "STEP_STEP") (pintype "bidirectional"))
      (node (ref "U$1") (pin "5") (pinfunction "5/PWM_5") (pintype "bidirectional"))
    )
    (net (code "77") (name "MSTEP_02") (class "Default")
      (node (ref "MOTOR_02") (pin "STEP") (pinfunction "STEP_STEP") (pintype "bidirectional"))
      (node (ref "U$1") (pin "7") (pinfunction "7/RX3_7") (pintype "bidirectional"))
    )
    (net (code "78") (name "MSTEP_03") (class "Default")
      (node (ref "MOTOR_03") (pin "STEP") (pinfunction "STEP_STEP") (pintype "bidirectional"))
      (node (ref "U$1") (pin "9") (pinfunction "9/RX2/PWM_9") (pintype "bidirectional"))
    )
    (net (code "79") (name "MSTEP_04") (class "Default")
      (node (ref "MOTOR_04") (pin "STEP") (pinfunction "STEP_STEP") (pintype "bidirectional"))
      (node (ref "U$1") (pin "14/A0") (pinfunction "14/A0_14/A0") (pintype "bidirectional"))
    )
    (net (code "80") (name "MSTEP_05") (class "Default")
      (node (ref "MOTOR_05") (pin "STEP") (pinfunction "STEP_STEP") (pintype "bidirectional"))
      (node (ref "U$1") (pin "16/A2") (pinfunction "16/A2/T_16/A2") (pintype "bidirectional"))
    )
    (net (code "81") (name "MSTEP_06") (class "Default")
      (node (ref "MOTOR_06") (pin "STEP") (pinfunction "STEP_STEP") (pintype "bidirectional"))
      (node (ref "U$1") (pin "20/A6") (pinfunction "20/A6/PWM_20/A6") (pintype "bidirectional"))
    )
    (net (code "82") (name "MSTEP_07") (class "Default")
      (node (ref "MOTOR_07") (pin "STEP") (pinfunction "STEP_STEP") (pintype "bidirectional"))
      (node (ref "U$1") (pin "22/A8") (pinfunction "22/A8/T/PWM_22/A8") (pintype "bidirectional"))
    )
    (net (code "83") (name "MSTEP_08") (class "Default")
      (node (ref "MOTOR_08") (pin "STEP") (pinfunction "STEP_STEP") (pintype "bidirectional"))
      (node (ref "U$1") (pin "24") (pinfunction "24_24") (pintype "bidirectional"))
    )
    (net (code "84") (name "MUS_S1") (class "Default")
      (node (ref "U1") (pin "11") (pinfunction "S1_11") (pintype "input"))
    )
    (net (code "85") (name "MUX_INT") (class "Default")
      (node (ref "J1") (pin "1") (pinfunction "1_1") (pintype "passive"))
    )
    (net (code "86") (name "MUX_OSCIO") (class "Default")
      (node (ref "J2") (pin "1") (pinfunction "1_1") (pintype "passive"))
    )
    (net (code "87") (name "MUX_RESET") (class "Default")
      (node (ref "J1") (pin "2") (pinfunction "2_2") (pintype "passive"))
      (node (ref "J2") (pin "2") (pinfunction "2_2") (pintype "passive"))
    )
    (net (code "88") (name "MUX_S0") (class "Default")
      (node (ref "U$1") (pin "26") (pinfunction "26/A15_26") (pintype "bidirectional"))
    )
    (net (code "89") (name "MUX_S1") (class "Default")
      (node (ref "U$1") (pin "27") (pinfunction "27/A16_27") (pintype "bidirectional"))
    )
    (net (code "90") (name "MUX_S2") (class "Default")
      (node (ref "U$1") (pin "28") (pinfunction "28/A17_28") (pintype "bidirectional"))
      (node (ref "U1") (pin "14") (pinfunction "S2_14") (pintype "input"))
    )
    (net (code "91") (name "MUX_S3") (class "Default")
      (node (ref "U$1") (pin "31") (pinfunction "31/A20_31") (pintype "bidirectional"))
      (node (ref "U1") (pin "13") (pinfunction "S3_13") (pintype "input"))
    )
    (net (code "92") (name "MUX_SCL") (class "Default")
      (node (ref "J1") (pin "6") (pinfunction "6_6") (pintype "passive"))
      (node (ref "J2") (pin "6") (pinfunction "6_6") (pintype "passive"))
      (node (ref "U$1") (pin "19/A5") (pinfunction "19/A5/T/SCL0_19/A5") (pintype "bidirectional"))
    )
    (net (code "93") (name "MUX_SDA") (class "Default")
      (node (ref "J1") (pin "5") (pinfunction "5_5") (pintype "passive"))
      (node (ref "J2") (pin "5") (pinfunction "5_5") (pintype "passive"))
      (node (ref "U$1") (pin "18/A4") (pinfunction "18/A4/T/SDA0_18/A4") (pintype "bidirectional"))
    )
    (net (code "94") (name "MUX_SIG") (class "Default")
      (node (ref "U$1") (pin "A13") (pinfunction "A13_A13") (pintype "bidirectional"))
      (node (ref "U1") (pin "1") (pinfunction "COM_1") (pintype "bidirectional"))
    )
    (net (code "95") (name "MUX_SO") (class "Default")
      (node (ref "U1") (pin "10") (pinfunction "S0_10") (pintype "input"))
    )
    (net (code "96") (name "NEO_PIXEL") (class "Default")
      (node (ref "CONN02") (pin "7") (pinfunction "7_7") (pintype "bidirectional"))
      (node (ref "U$1") (pin "2") (pinfunction "2_2") (pintype "bidirectional"))
    )
    (net (code "97") (name "Net-(CAN_LED-A)") (class "Default")
      (node (ref "CAN_LED") (pin "1") (pinfunction "A_1") (pintype "passive"))
      (node (ref "CAN_LED_R") (pin "1") (pinfunction "1_1") (pintype "passive"))
    )
    (net (code "98") (name "Net-(POWER_LED-A)") (class "Default")
      (node (ref "POWER_LED") (pin "1") (pinfunction "A_1") (pintype "passive"))
      (node (ref "POWER_LED_RES") (pin "1") (pinfunction "1_1") (pintype "passive"))
    )
    (net (code "99") (name "Net-(U1-CHAN0)") (class "Default")
      (node (ref "SW1") (pin "20") (pinfunction "20_20") (pintype "passive"))
      (node (ref "U1") (pin "9") (pinfunction "CHAN0_9") (pintype "bidirectional"))
    )
    (net (code "100") (name "Net-(U1-CHAN1)") (class "Default")
      (node (ref "SW1") (pin "19") (pinfunction "19_19") (pintype "passive"))
      (node (ref "U1") (pin "8") (pinfunction "CHAN1_8") (pintype "bidirectional"))
    )
    (net (code "101") (name "Net-(U1-CHAN2)") (class "Default")
      (node (ref "SW1") (pin "18") (pinfunction "18_18") (pintype "passive"))
      (node (ref "U1") (pin "7") (pinfunction "CHAN2_7") (pintype "bidirectional"))
    )
    (net (code "102") (name "Net-(U1-CHAN3)") (class "Default")
      (node (ref "SW1") (pin "17") (pinfunction "17_17") (pintype "passive"))
      (node (ref "U1") (pin "6") (pinfunction "CHAN3_6") (pintype "bidirectional"))
    )
    (net (code "103") (name "Net-(U1-CHAN4)") (class "Default")
      (node (ref "SW1") (pin "16") (pinfunction "16_16") (pintype "passive"))
      (node (ref "U1") (pin "5") (pinfunction "CHAN4_5") (pintype "bidirectional"))
    )
    (net (code "104") (name "Net-(U1-CHAN5)") (class "Default")
      (node (ref "SW1") (pin "15") (pinfunction "15_15") (pintype "passive"))
      (node (ref "U1") (pin "4") (pinfunction "CHAN5_4") (pintype "bidirectional"))
    )
    (net (code "105") (name "Net-(U1-CHAN6)") (class "Default")
      (node (ref "SW1") (pin "14") (pinfunction "14_14") (pintype "passive"))
      (node (ref "U1") (pin "3") (pinfunction "CHAN6_3") (pintype "bidirectional"))
    )
    (net (code "106") (name "Net-(U1-CHAN7)") (class "Default")
      (node (ref "SW1") (pin "13") (pinfunction "13_13") (pintype "passive"))
      (node (ref "U1") (pin "2") (pinfunction "CHAN7_2") (pintype "bidirectional"))
    )
    (net (code "107") (name "Net-(U1-CHAN8)") (class "Default")
      (node (ref "SW1") (pin "12") (pinfunction "12_12") (pintype "passive"))
      (node (ref "U1") (pin "23") (pinfunction "CHAN8_23") (pintype "bidirectional"))
    )
    (net (code "108") (name "Net-(U1-CHAN9)") (class "Default")
      (node (ref "SW1") (pin "11") (pinfunction "11_11") (pintype "passive"))
      (node (ref "U1") (pin "22") (pinfunction "CHAN9_22") (pintype "bidirectional"))
    )
    (net (code "109") (name "S_SCL") (class "Default")
      (node (ref "CONN02") (pin "10") (pinfunction "10_10") (pintype "bidirectional"))
      (node (ref "U$1") (pin "29") (pinfunction "29/A18/SCL1_29") (pintype "bidirectional"))
    )
    (net (code "110") (name "S_SDA") (class "Default")
      (node (ref "CONN02") (pin "9") (pinfunction "9_9") (pintype "bidirectional"))
      (node (ref "U$1") (pin "30") (pinfunction "30/A19/SDA1_30") (pintype "bidirectional"))
    )
    (net (code "111") (name "S_SEN_01") (class "Default")
      (node (ref "CONN02") (pin "8") (pinfunction "8_8") (pintype "bidirectional"))
      (node (ref "U$1") (pin "A12") (pinfunction "A12_A12") (pintype "bidirectional"))
    )
    (net (code "112") (name "VCC1") (class "Default")
      (node (ref "J3") (pin "5") (pinfunction "5_5") (pintype "passive"))
    )
    (net (code "113") (name "VCC2") (class "Default")
      (node (ref "J4") (pin "5") (pinfunction "5_5") (pintype "passive"))
    )
    (net (code "114") (name "VCC_IN") (class "Default")
      (node (ref "INPUT_POWER_1") (pin "VCC_01") (pinfunction "VCC_01_VCC_01") (pintype "bidirectional"))
      (node (ref "INPUT_POWER_1") (pin "VCC_02") (pinfunction "VCC_02_VCC_02") (pintype "bidirectional"))
      (node (ref "INPUT_POWER_2") (pin "VCC_01") (pinfunction "VCC_01_VCC_01") (pintype "bidirectional"))
      (node (ref "INPUT_POWER_2") (pin "VCC_02") (pinfunction "VCC_02_VCC_02") (pintype "bidirectional"))
    )
    (net (code "115") (name "VCC_M") (class "Default")
      (node (ref "MOTOR_01") (pin "VCC") (pinfunction "VCC_VCC") (pintype "bidirectional"))
      (node (ref "MOTOR_02") (pin "VCC") (pinfunction "VCC_VCC") (pintype "bidirectional"))
      (node (ref "MOTOR_03") (pin "VCC") (pinfunction "VCC_VCC") (pintype "bidirectional"))
      (node (ref "MOTOR_04") (pin "VCC") (pinfunction "VCC_VCC") (pintype "bidirectional"))
      (node (ref "MOTOR_05") (pin "VCC") (pinfunction "VCC_VCC") (pintype "bidirectional"))
      (node (ref "MOTOR_06") (pin "VCC") (pinfunction "VCC_VCC") (pintype "bidirectional"))
      (node (ref "MOTOR_07") (pin "VCC") (pinfunction "VCC_VCC") (pintype "bidirectional"))
      (node (ref "MOTOR_08") (pin "VCC") (pinfunction "VCC_VCC") (pintype "bidirectional"))
      (node (ref "M_C10") (pin "1") (pinfunction "1_1") (pintype "passive"))
      (node (ref "M_C11") (pin "1") (pinfunction "1_1") (pintype "passive"))
      (node (ref "M_C4") (pin "1") (pinfunction "1_1") (pintype "passive"))
      (node (ref "M_C5") (pin "1") (pinfunction "1_1") (pintype "passive"))
      (node (ref "M_C6") (pin "1") (pinfunction "1_1") (pintype "passive"))
      (node (ref "M_C7") (pin "1") (pinfunction "1_1") (pintype "passive"))
      (node (ref "M_C8") (pin "1") (pinfunction "1_1") (pintype "passive"))
      (node (ref "M_C9") (pin "1") (pinfunction "1_1") (pintype "passive"))
      (node (ref "OUTPUT_POWER") (pin "VCC_01") (pinfunction "VCC_01_VCC_01") (pintype "bidirectional"))
      (node (ref "POWER_LED_RES") (pin "2") (pinfunction "2_2") (pintype "passive"))
    )
    (net (code "116") (name "VCC_MCU") (class "Default")
      (node (ref "C2") (pin "2") (pinfunction "2_2") (pintype "passive"))
      (node (ref "C3") (pin "1") (pinfunction "1_1") (pintype "passive"))
      (node (ref "CONN01") (pin "11") (pinfunction "11_11") (pintype "bidirectional"))
      (node (ref "CONN02") (pin "11") (pinfunction "11_11") (pintype "bidirectional"))
      (node (ref "OUTPUT_POWER") (pin "VCC_02") (pinfunction "VCC_02_VCC_02") (pintype "bidirectional"))
      (node (ref "TCAN1042") (pin "3") (pinfunction "VCC_3") (pintype "power_in"))
      (node (ref "U$1") (pin "VIN") (pinfunction "VIN_VIN") (pintype "power_in"))
    )
    (net (code "117") (name "unconnected-(J3-Pad10)") (class "Default")
      (node (ref "J3") (pin "10") (pinfunction "10_10") (pintype "passive"))
    )
    (net (code "118") (name "unconnected-(J4-Pad10)") (class "Default")
      (node (ref "J4") (pin "10") (pinfunction "10_10") (pintype "passive"))
    )
    (net (code "119") (name "unconnected-(MOTOR_01-Pad1)") (class "Default")
      (node (ref "MOTOR_01") (pin "1") (pinfunction "1_1") (pintype "bidirectional"))
    )
    (net (code "120") (name "unconnected-(MOTOR_01-Pad2)") (class "Default")
      (node (ref "MOTOR_01") (pin "2") (pinfunction "2_2") (pintype "bidirectional"))
    )
    (net (code "121") (name "unconnected-(MOTOR_01-PadSTBY)") (class "Default")
      (node (ref "MOTOR_01") (pin "STBY") (pinfunction "STBY_STBY") (pintype "bidirectional"))
    )
    (net (code "122") (name "unconnected-(MOTOR_01-PadVMOT)") (class "Default")
      (node (ref "MOTOR_01") (pin "VMOT") (pinfunction "VMOT_VMOT") (pintype "bidirectional"))
    )
    (net (code "123") (name "unconnected-(MOTOR_02-Pad1)") (class "Default")
      (node (ref "MOTOR_02") (pin "1") (pinfunction "1_1") (pintype "bidirectional"))
    )
    (net (code "124") (name "unconnected-(MOTOR_02-Pad2)") (class "Default")
      (node (ref "MOTOR_02") (pin "2") (pinfunction "2_2") (pintype "bidirectional"))
    )
    (net (code "125") (name "unconnected-(MOTOR_02-PadSTBY)") (class "Default")
      (node (ref "MOTOR_02") (pin "STBY") (pinfunction "STBY_STBY") (pintype "bidirectional"))
    )
    (net (code "126") (name "unconnected-(MOTOR_02-PadVMOT)") (class "Default")
      (node (ref "MOTOR_02") (pin "VMOT") (pinfunction "VMOT_VMOT") (pintype "bidirectional"))
    )
    (net (code "127") (name "unconnected-(MOTOR_03-Pad1)") (class "Default")
      (node (ref "MOTOR_03") (pin "1") (pinfunction "1_1") (pintype "bidirectional"))
    )
    (net (code "128") (name "unconnected-(MOTOR_03-Pad2)") (class "Default")
      (node (ref "MOTOR_03") (pin "2") (pinfunction "2_2") (pintype "bidirectional"))
    )
    (net (code "129") (name "unconnected-(MOTOR_03-PadSTBY)") (class "Default")
      (node (ref "MOTOR_03") (pin "STBY") (pinfunction "STBY_STBY") (pintype "bidirectional"))
    )
    (net (code "130") (name "unconnected-(MOTOR_03-PadVMOT)") (class "Default")
      (node (ref "MOTOR_03") (pin "VMOT") (pinfunction "VMOT_VMOT") (pintype "bidirectional"))
    )
    (net (code "131") (name "unconnected-(MOTOR_04-Pad1)") (class "Default")
      (node (ref "MOTOR_04") (pin "1") (pinfunction "1_1") (pintype "bidirectional"))
    )
    (net (code "132") (name "unconnected-(MOTOR_04-Pad2)") (class "Default")
      (node (ref "MOTOR_04") (pin "2") (pinfunction "2_2") (pintype "bidirectional"))
    )
    (net (code "133") (name "unconnected-(MOTOR_04-PadSTBY)") (class "Default")
      (node (ref "MOTOR_04") (pin "STBY") (pinfunction "STBY_STBY") (pintype "bidirectional"))
    )
    (net (code "134") (name "unconnected-(MOTOR_04-PadVMOT)") (class "Default")
      (node (ref "MOTOR_04") (pin "VMOT") (pinfunction "VMOT_VMOT") (pintype "bidirectional"))
    )
    (net (code "135") (name "unconnected-(MOTOR_05-Pad1)") (class "Default")
      (node (ref "MOTOR_05") (pin "1") (pinfunction "1_1") (pintype "bidirectional"))
    )
    (net (code "136") (name "unconnected-(MOTOR_05-Pad2)") (class "Default")
      (node (ref "MOTOR_05") (pin "2") (pinfunction "2_2") (pintype "bidirectional"))
    )
    (net (code "137") (name "unconnected-(MOTOR_05-PadSTBY)") (class "Default")
      (node (ref "MOTOR_05") (pin "STBY") (pinfunction "STBY_STBY") (pintype "bidirectional"))
    )
    (net (code "138") (name "unconnected-(MOTOR_05-PadVMOT)") (class "Default")
      (node (ref "MOTOR_05") (pin "VMOT") (pinfunction "VMOT_VMOT") (pintype "bidirectional"))
    )
    (net (code "139") (name "unconnected-(MOTOR_06-Pad1)") (class "Default")
      (node (ref "MOTOR_06") (pin "1") (pinfunction "1_1") (pintype "bidirectional"))
    )
    (net (code "140") (name "unconnected-(MOTOR_06-Pad2)") (class "Default")
      (node (ref "MOTOR_06") (pin "2") (pinfunction "2_2") (pintype "bidirectional"))
    )
    (net (code "141") (name "unconnected-(MOTOR_06-PadSTBY)") (class "Default")
      (node (ref "MOTOR_06") (pin "STBY") (pinfunction "STBY_STBY") (pintype "bidirectional"))
    )
    (net (code "142") (name "unconnected-(MOTOR_06-PadVMOT)") (class "Default")
      (node (ref "MOTOR_06") (pin "VMOT") (pinfunction "VMOT_VMOT") (pintype "bidirectional"))
    )
    (net (code "143") (name "unconnected-(MOTOR_07-Pad1)") (class "Default")
      (node (ref "MOTOR_07") (pin "1") (pinfunction "1_1") (pintype "bidirectional"))
    )
    (net (code "144") (name "unconnected-(MOTOR_07-Pad2)") (class "Default")
      (node (ref "MOTOR_07") (pin "2") (pinfunction "2_2") (pintype "bidirectional"))
    )
    (net (code "145") (name "unconnected-(MOTOR_07-PadSTBY)") (class "Default")
      (node (ref "MOTOR_07") (pin "STBY") (pinfunction "STBY_STBY") (pintype "bidirectional"))
    )
    (net (code "146") (name "unconnected-(MOTOR_07-PadVMOT)") (class "Default")
      (node (ref "MOTOR_07") (pin "VMOT") (pinfunction "VMOT_VMOT") (pintype "bidirectional"))
    )
    (net (code "147") (name "unconnected-(MOTOR_08-Pad1)") (class "Default")
      (node (ref "MOTOR_08") (pin "1") (pinfunction "1_1") (pintype "bidirectional"))
    )
    (net (code "148") (name "unconnected-(MOTOR_08-Pad2)") (class "Default")
      (node (ref "MOTOR_08") (pin "2") (pinfunction "2_2") (pintype "bidirectional"))
    )
    (net (code "149") (name "unconnected-(MOTOR_08-PadSTBY)") (class "Default")
      (node (ref "MOTOR_08") (pin "STBY") (pinfunction "STBY_STBY") (pintype "bidirectional"))
    )
    (net (code "150") (name "unconnected-(MOTOR_08-PadVMOT)") (class "Default")
      (node (ref "MOTOR_08") (pin "VMOT") (pinfunction "VMOT_VMOT") (pintype "bidirectional"))
    )
    (net (code "151") (name "unconnected-(TCAN1042-NC-Pad5)") (class "Default")
      (node (ref "TCAN1042") (pin "5") (pinfunction "NC_5") (pintype "passive"))
    )
    (net (code "152") (name "unconnected-(U$1-0{slash}RX1{slash}T-Pad0)") (class "Default")
      (node (ref "U$1") (pin "0") (pinfunction "0/RX1/T_0") (pintype "bidirectional"))
    )
    (net (code "153") (name "unconnected-(U$1-1{slash}TX1{slash}T-Pad1)") (class "Default")
      (node (ref "U$1") (pin "1") (pinfunction "1/TX1/T_1") (pintype "bidirectional"))
    )
    (net (code "154") (name "unconnected-(U$1-13{slash}SCK{slash}LED-Pad13)") (class "Default")
      (node (ref "U$1") (pin "13") (pinfunction "13/SCK/LED_13") (pintype "bidirectional"))
    )
    (net (code "155") (name "unconnected-(U$1-A14{slash}DAC-PadRESET{slash}DAC)") (class "Default")
      (node (ref "U$1") (pin "RESET/DAC") (pinfunction "A14/DAC_RESET/DAC") (pintype "bidirectional"))
    )
    (net (code "156") (name "unconnected-(U$1-PadA10)") (class "Default")
      (node (ref "U$1") (pin "A10") (pinfunction "A10_A10") (pintype "bidirectional"))
    )
    (net (code "157") (name "unconnected-(U$1-PadA11)") (class "Default")
      (node (ref "U$1") (pin "A11") (pinfunction "A11_A11") (pintype "bidirectional"))
    )
    (net (code "158") (name "unconnected-(U$1-PadPGM)") (class "Default")
      (node (ref "U$1") (pin "PGM") (pinfunction "PGM_PGM") (pintype "bidirectional"))
    )
    (net (code "159") (name "unconnected-(U1-CHAN10-Pad21)") (class "Default")
      (node (ref "U1") (pin "21") (pinfunction "CHAN10_21") (pintype "bidirectional"))
    )
    (net (code "160") (name "unconnected-(U1-CHAN11-Pad20)") (class "Default")
      (node (ref "U1") (pin "20") (pinfunction "CHAN11_20") (pintype "bidirectional"))
    )
    (net (code "161") (name "unconnected-(U1-CHAN12-Pad19)") (class "Default")
      (node (ref "U1") (pin "19") (pinfunction "CHAN12_19") (pintype "bidirectional"))
    )
    (net (code "162") (name "unconnected-(U1-CHAN13-Pad18)") (class "Default")
      (node (ref "U1") (pin "18") (pinfunction "CHAN13_18") (pintype "bidirectional"))
    )
    (net (code "163") (name "unconnected-(U1-CHAN14-Pad17)") (class "Default")
      (node (ref "U1") (pin "17") (pinfunction "CHAN14_17") (pintype "bidirectional"))
    )
    (net (code "164") (name "unconnected-(U1-CHAN15-Pad16)") (class "Default")
      (node (ref "U1") (pin "16") (pinfunction "CHAN15_16") (pintype "bidirectional"))
    )
  )
)
